# 601_USBHub-Grid-Part1.net
KiCad netlist of a schematic drawn in Altium Designer
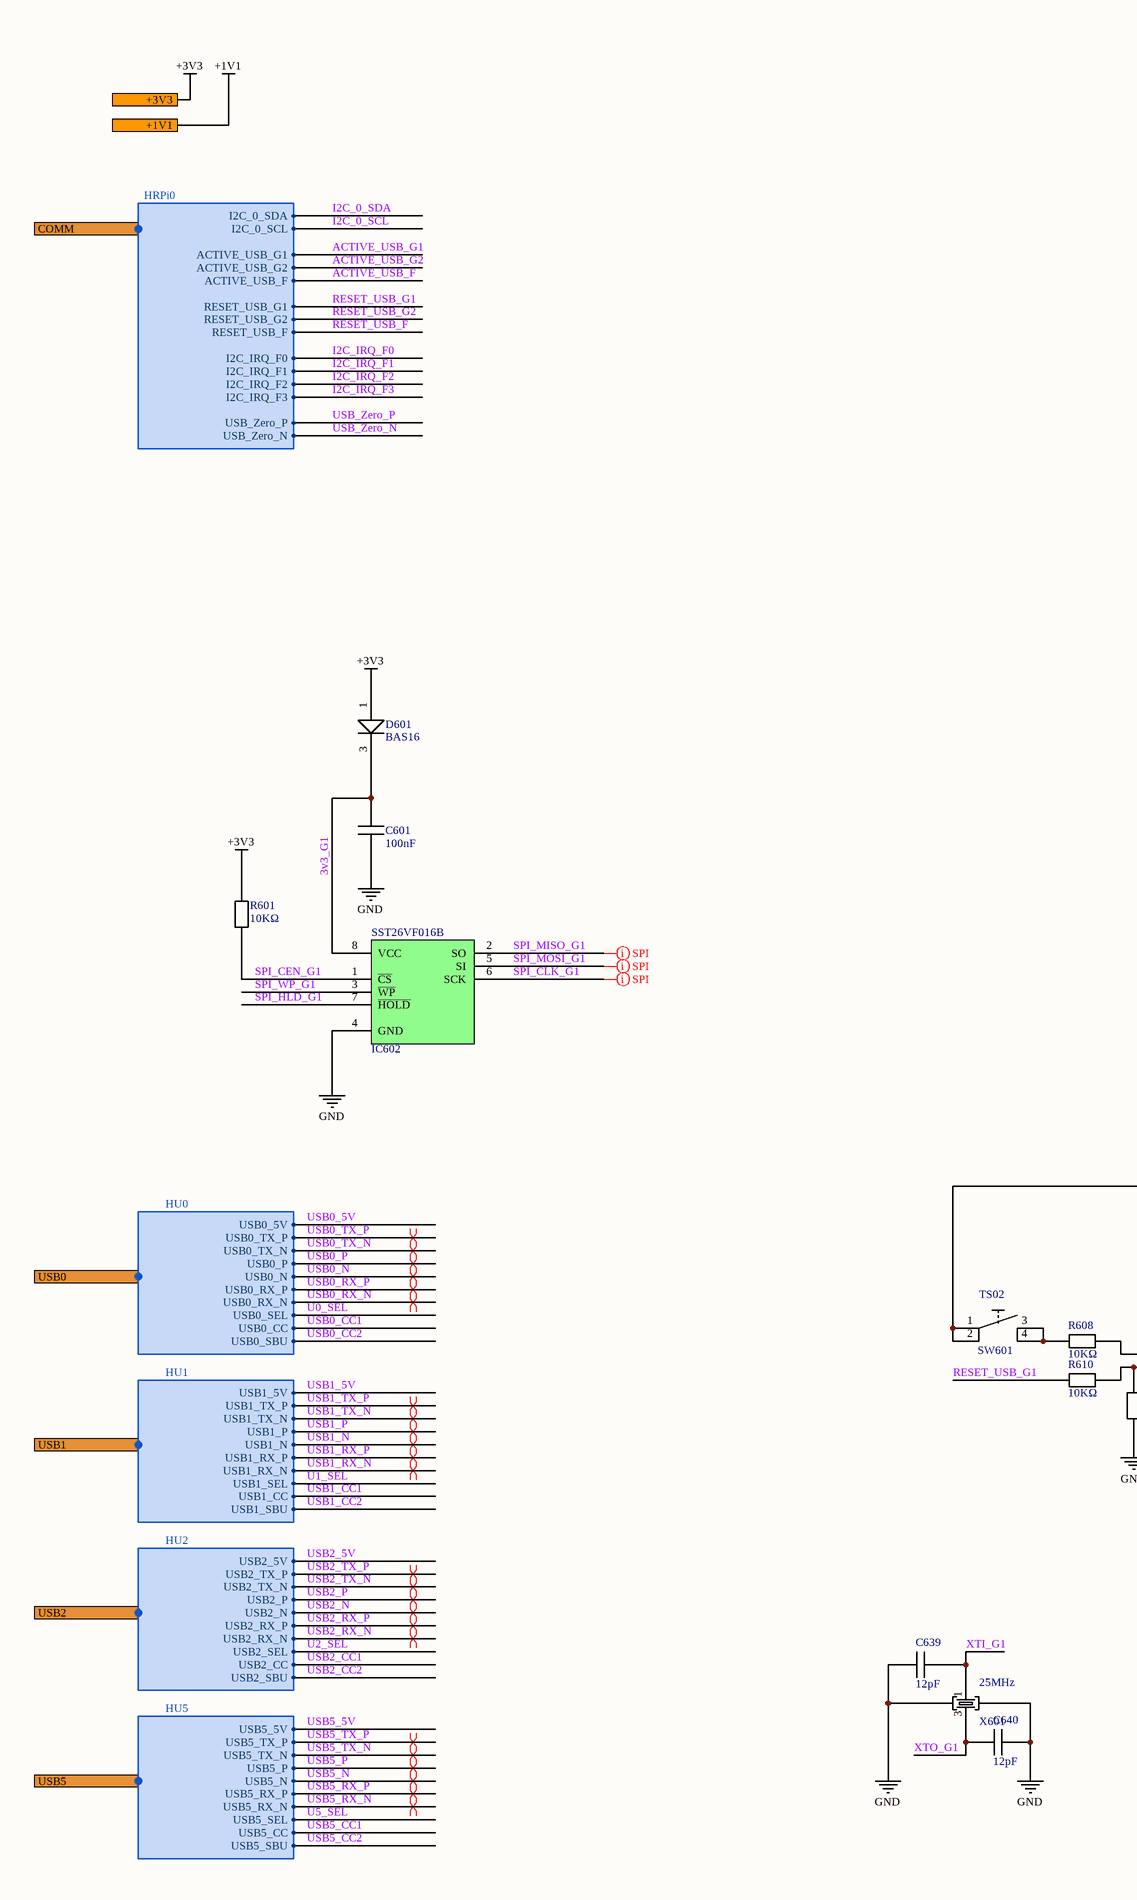
[diagram p0: 601_USBHub-Grid-Part1.SchDoc, left]
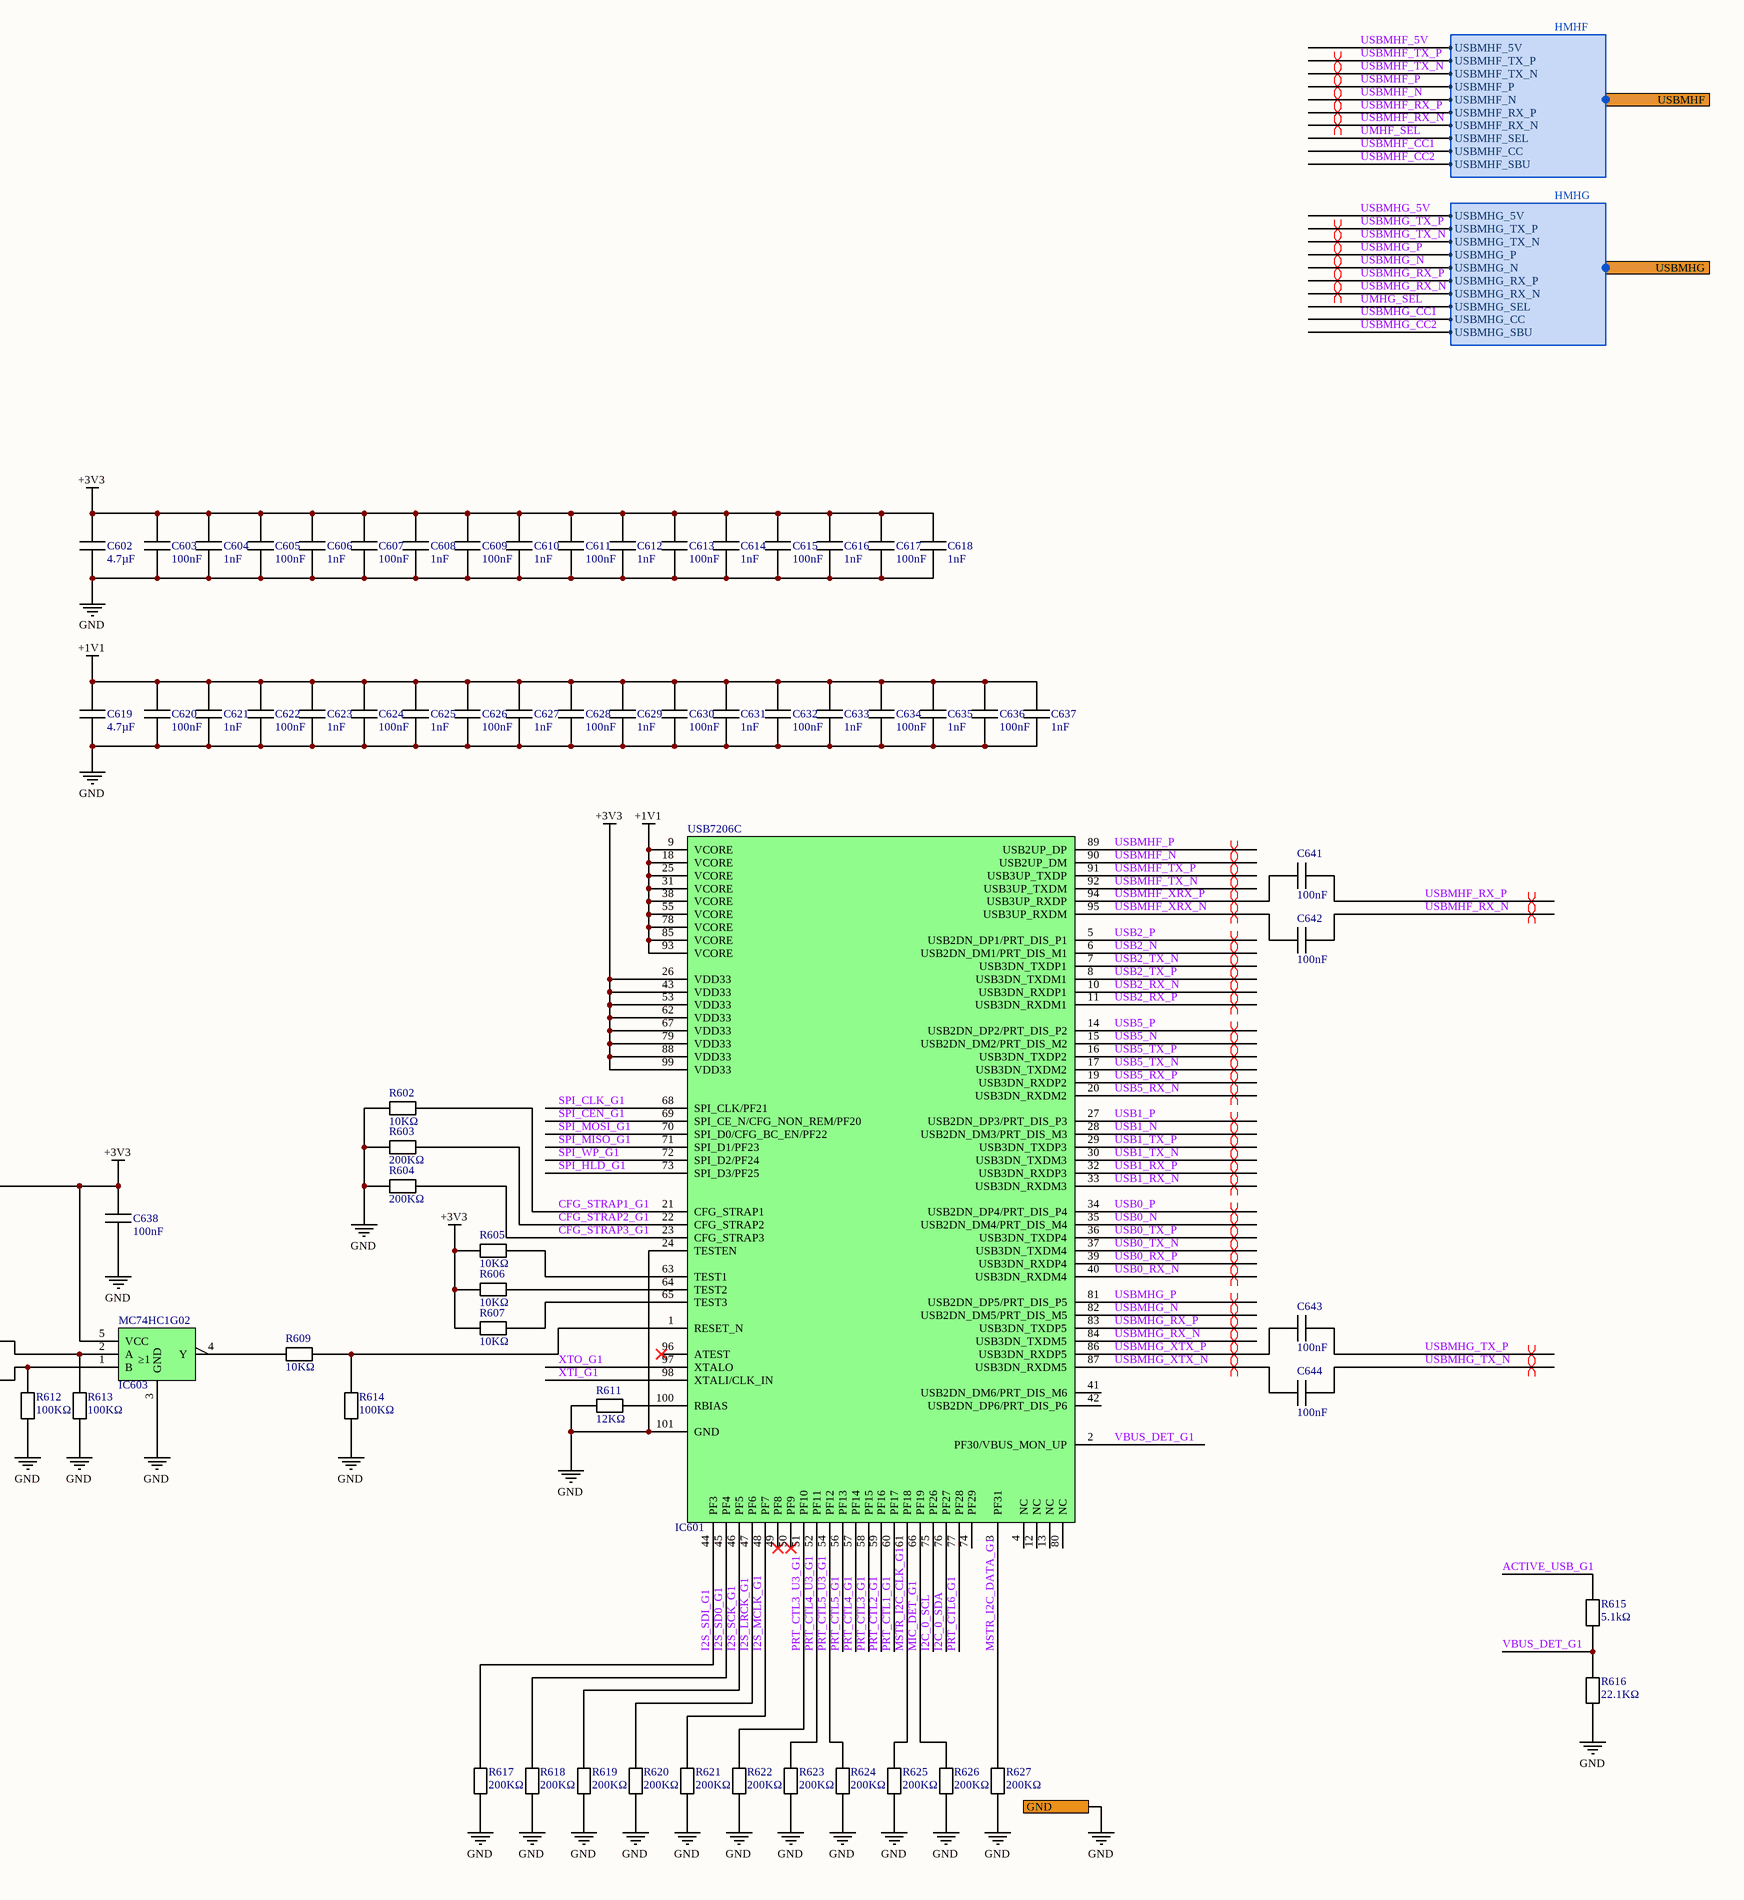
[diagram p1: 601_USBHub-Grid-Part1.SchDoc, right]

(export (version "E")
  (design (tool "Eeschema 10.0.6"))
  (components
    (comp (ref "C601")
      (value "100nF")
      (footprint "C0402")
      (description "100nF 16V 10% X7R")
      (fields
        (field (name "REFVAL") "100nF")
        (field (name "PART NUMBER") "CA0010")
        (field (name "MANFACTPART") "GCM155R71C104KA55D")
      )
      (libsource (lib "GTS_Database") (part "C"))
    )
    (comp (ref "C602")
      (value "4.7µF")
      (footprint "C0603")
      (description "4.7µF 16V 10% X5R")
      (fields
        (field (name "REFVAL") "4.7µF")
        (field (name "PART NUMBER") "CA0002")
        (field (name "MANFACTPART") "C1608X5R1C475K080AC")
      )
      (libsource (lib "GTS_Database") (part "C"))
    )
    (comp (ref "C603")
      (value "100nF")
      (footprint "C0402")
      (description "100nF 16V 10% X7R")
      (fields
        (field (name "REFVAL") "100nF")
        (field (name "PART NUMBER") "CA0010")
        (field (name "MANFACTPART") "GCM155R71C104KA55D")
      )
      (libsource (lib "GTS_Database") (part "C"))
    )
    (comp (ref "C604")
      (value "1nF")
      (footprint "C0402")
      (description "1nF 50V 1% C0G")
      (fields
        (field (name "REFVAL") "1nF")
        (field (name "PART NUMBER") "CA0031")
        (field (name "MANFACTPART") "GRT1555C1H102FA02D")
      )
      (libsource (lib "GTS_Database") (part "C"))
    )
    (comp (ref "C605")
      (value "100nF")
      (footprint "C0402")
      (description "100nF 16V 10% X7R")
      (fields
        (field (name "REFVAL") "100nF")
        (field (name "PART NUMBER") "CA0010")
        (field (name "MANFACTPART") "GCM155R71C104KA55D")
      )
      (libsource (lib "GTS_Database") (part "C"))
    )
    (comp (ref "C606")
      (value "1nF")
      (footprint "C0402")
      (description "1nF 50V 1% C0G")
      (fields
        (field (name "REFVAL") "1nF")
        (field (name "PART NUMBER") "CA0031")
        (field (name "MANFACTPART") "GRT1555C1H102FA02D")
      )
      (libsource (lib "GTS_Database") (part "C"))
    )
    (comp (ref "C607")
      (value "100nF")
      (footprint "C0402")
      (description "100nF 16V 10% X7R")
      (fields
        (field (name "REFVAL") "100nF")
        (field (name "PART NUMBER") "CA0010")
        (field (name "MANFACTPART") "GCM155R71C104KA55D")
      )
      (libsource (lib "GTS_Database") (part "C"))
    )
    (comp (ref "C608")
      (value "1nF")
      (footprint "C0402")
      (description "1nF 50V 1% C0G")
      (fields
        (field (name "REFVAL") "1nF")
        (field (name "PART NUMBER") "CA0031")
        (field (name "MANFACTPART") "GRT1555C1H102FA02D")
      )
      (libsource (lib "GTS_Database") (part "C"))
    )
    (comp (ref "C609")
      (value "100nF")
      (footprint "C0402")
      (description "100nF 16V 10% X7R")
      (fields
        (field (name "REFVAL") "100nF")
        (field (name "PART NUMBER") "CA0010")
        (field (name "MANFACTPART") "GCM155R71C104KA55D")
      )
      (libsource (lib "GTS_Database") (part "C"))
    )
    (comp (ref "C610")
      (value "1nF")
      (footprint "C0402")
      (description "1nF 50V 1% C0G")
      (fields
        (field (name "REFVAL") "1nF")
        (field (name "PART NUMBER") "CA0031")
        (field (name "MANFACTPART") "GRT1555C1H102FA02D")
      )
      (libsource (lib "GTS_Database") (part "C"))
    )
    (comp (ref "C611")
      (value "100nF")
      (footprint "C0402")
      (description "100nF 16V 10% X7R")
      (fields
        (field (name "REFVAL") "100nF")
        (field (name "PART NUMBER") "CA0010")
        (field (name "MANFACTPART") "GCM155R71C104KA55D")
      )
      (libsource (lib "GTS_Database") (part "C"))
    )
    (comp (ref "C612")
      (value "1nF")
      (footprint "C0402")
      (description "1nF 50V 1% C0G")
      (fields
        (field (name "REFVAL") "1nF")
        (field (name "PART NUMBER") "CA0031")
        (field (name "MANFACTPART") "GRT1555C1H102FA02D")
      )
      (libsource (lib "GTS_Database") (part "C"))
    )
    (comp (ref "C613")
      (value "100nF")
      (footprint "C0402")
      (description "100nF 16V 10% X7R")
      (fields
        (field (name "REFVAL") "100nF")
        (field (name "PART NUMBER") "CA0010")
        (field (name "MANFACTPART") "GCM155R71C104KA55D")
      )
      (libsource (lib "GTS_Database") (part "C"))
    )
    (comp (ref "C614")
      (value "1nF")
      (footprint "C0402")
      (description "1nF 50V 1% C0G")
      (fields
        (field (name "REFVAL") "1nF")
        (field (name "PART NUMBER") "CA0031")
        (field (name "MANFACTPART") "GRT1555C1H102FA02D")
      )
      (libsource (lib "GTS_Database") (part "C"))
    )
    (comp (ref "C615")
      (value "100nF")
      (footprint "C0402")
      (description "100nF 16V 10% X7R")
      (fields
        (field (name "REFVAL") "100nF")
        (field (name "PART NUMBER") "CA0010")
        (field (name "MANFACTPART") "GCM155R71C104KA55D")
      )
      (libsource (lib "GTS_Database") (part "C"))
    )
    (comp (ref "C616")
      (value "1nF")
      (footprint "C0402")
      (description "1nF 50V 1% C0G")
      (fields
        (field (name "REFVAL") "1nF")
        (field (name "PART NUMBER") "CA0031")
        (field (name "MANFACTPART") "GRT1555C1H102FA02D")
      )
      (libsource (lib "GTS_Database") (part "C"))
    )
    (comp (ref "C617")
      (value "100nF")
      (footprint "C0402")
      (description "100nF 16V 10% X7R")
      (fields
        (field (name "REFVAL") "100nF")
        (field (name "PART NUMBER") "CA0010")
        (field (name "MANFACTPART") "GCM155R71C104KA55D")
      )
      (libsource (lib "GTS_Database") (part "C"))
    )
    (comp (ref "C618")
      (value "1nF")
      (footprint "C0402")
      (description "1nF 50V 1% C0G")
      (fields
        (field (name "REFVAL") "1nF")
        (field (name "PART NUMBER") "CA0031")
        (field (name "MANFACTPART") "GRT1555C1H102FA02D")
      )
      (libsource (lib "GTS_Database") (part "C"))
    )
    (comp (ref "C619")
      (value "4.7µF")
      (footprint "C0603")
      (description "4.7µF 16V 10% X5R")
      (fields
        (field (name "REFVAL") "4.7µF")
        (field (name "PART NUMBER") "CA0002")
        (field (name "MANFACTPART") "C1608X5R1C475K080AC")
      )
      (libsource (lib "GTS_Database") (part "C"))
    )
    (comp (ref "C620")
      (value "100nF")
      (footprint "C0402")
      (description "100nF 16V 10% X7R")
      (fields
        (field (name "REFVAL") "100nF")
        (field (name "PART NUMBER") "CA0010")
        (field (name "MANFACTPART") "GCM155R71C104KA55D")
      )
      (libsource (lib "GTS_Database") (part "C"))
    )
    (comp (ref "C621")
      (value "1nF")
      (footprint "C0402")
      (description "1nF 50V 1% C0G")
      (fields
        (field (name "REFVAL") "1nF")
        (field (name "PART NUMBER") "CA0031")
        (field (name "MANFACTPART") "GRT1555C1H102FA02D")
      )
      (libsource (lib "GTS_Database") (part "C"))
    )
    (comp (ref "C622")
      (value "100nF")
      (footprint "C0402")
      (description "100nF 16V 10% X7R")
      (fields
        (field (name "REFVAL") "100nF")
        (field (name "PART NUMBER") "CA0010")
        (field (name "MANFACTPART") "GCM155R71C104KA55D")
      )
      (libsource (lib "GTS_Database") (part "C"))
    )
    (comp (ref "C623")
      (value "1nF")
      (footprint "C0402")
      (description "1nF 50V 1% C0G")
      (fields
        (field (name "REFVAL") "1nF")
        (field (name "PART NUMBER") "CA0031")
        (field (name "MANFACTPART") "GRT1555C1H102FA02D")
      )
      (libsource (lib "GTS_Database") (part "C"))
    )
    (comp (ref "C624")
      (value "100nF")
      (footprint "C0402")
      (description "100nF 16V 10% X7R")
      (fields
        (field (name "REFVAL") "100nF")
        (field (name "PART NUMBER") "CA0010")
        (field (name "MANFACTPART") "GCM155R71C104KA55D")
      )
      (libsource (lib "GTS_Database") (part "C"))
    )
    (comp (ref "C625")
      (value "1nF")
      (footprint "C0402")
      (description "1nF 50V 1% C0G")
      (fields
        (field (name "REFVAL") "1nF")
        (field (name "PART NUMBER") "CA0031")
        (field (name "MANFACTPART") "GRT1555C1H102FA02D")
      )
      (libsource (lib "GTS_Database") (part "C"))
    )
    (comp (ref "C626")
      (value "100nF")
      (footprint "C0402")
      (description "100nF 16V 10% X7R")
      (fields
        (field (name "REFVAL") "100nF")
        (field (name "PART NUMBER") "CA0010")
        (field (name "MANFACTPART") "GCM155R71C104KA55D")
      )
      (libsource (lib "GTS_Database") (part "C"))
    )
    (comp (ref "C627")
      (value "1nF")
      (footprint "C0402")
      (description "1nF 50V 1% C0G")
      (fields
        (field (name "REFVAL") "1nF")
        (field (name "PART NUMBER") "CA0031")
        (field (name "MANFACTPART") "GRT1555C1H102FA02D")
      )
      (libsource (lib "GTS_Database") (part "C"))
    )
    (comp (ref "C628")
      (value "100nF")
      (footprint "C0402")
      (description "100nF 16V 10% X7R")
      (fields
        (field (name "REFVAL") "100nF")
        (field (name "PART NUMBER") "CA0010")
        (field (name "MANFACTPART") "GCM155R71C104KA55D")
      )
      (libsource (lib "GTS_Database") (part "C"))
    )
    (comp (ref "C629")
      (value "1nF")
      (footprint "C0402")
      (description "1nF 50V 1% C0G")
      (fields
        (field (name "REFVAL") "1nF")
        (field (name "PART NUMBER") "CA0031")
        (field (name "MANFACTPART") "GRT1555C1H102FA02D")
      )
      (libsource (lib "GTS_Database") (part "C"))
    )
    (comp (ref "C630")
      (value "100nF")
      (footprint "C0402")
      (description "100nF 16V 10% X7R")
      (fields
        (field (name "REFVAL") "100nF")
        (field (name "PART NUMBER") "CA0010")
        (field (name "MANFACTPART") "GCM155R71C104KA55D")
      )
      (libsource (lib "GTS_Database") (part "C"))
    )
    (comp (ref "C631")
      (value "1nF")
      (footprint "C0402")
      (description "1nF 50V 1% C0G")
      (fields
        (field (name "REFVAL") "1nF")
        (field (name "PART NUMBER") "CA0031")
        (field (name "MANFACTPART") "GRT1555C1H102FA02D")
      )
      (libsource (lib "GTS_Database") (part "C"))
    )
    (comp (ref "C632")
      (value "100nF")
      (footprint "C0402")
      (description "100nF 16V 10% X7R")
      (fields
        (field (name "REFVAL") "100nF")
        (field (name "PART NUMBER") "CA0010")
        (field (name "MANFACTPART") "GCM155R71C104KA55D")
      )
      (libsource (lib "GTS_Database") (part "C"))
    )
    (comp (ref "C633")
      (value "1nF")
      (footprint "C0402")
      (description "1nF 50V 1% C0G")
      (fields
        (field (name "REFVAL") "1nF")
        (field (name "PART NUMBER") "CA0031")
        (field (name "MANFACTPART") "GRT1555C1H102FA02D")
      )
      (libsource (lib "GTS_Database") (part "C"))
    )
    (comp (ref "C634")
      (value "100nF")
      (footprint "C0402")
      (description "100nF 16V 10% X7R")
      (fields
        (field (name "REFVAL") "100nF")
        (field (name "PART NUMBER") "CA0010")
        (field (name "MANFACTPART") "GCM155R71C104KA55D")
      )
      (libsource (lib "GTS_Database") (part "C"))
    )
    (comp (ref "C635")
      (value "1nF")
      (footprint "C0402")
      (description "1nF 50V 1% C0G")
      (fields
        (field (name "REFVAL") "1nF")
        (field (name "PART NUMBER") "CA0031")
        (field (name "MANFACTPART") "GRT1555C1H102FA02D")
      )
      (libsource (lib "GTS_Database") (part "C"))
    )
    (comp (ref "C636")
      (value "100nF")
      (footprint "C0402")
      (description "100nF 16V 10% X7R")
      (fields
        (field (name "REFVAL") "100nF")
        (field (name "PART NUMBER") "CA0010")
        (field (name "MANFACTPART") "GCM155R71C104KA55D")
      )
      (libsource (lib "GTS_Database") (part "C"))
    )
    (comp (ref "C637")
      (value "1nF")
      (footprint "C0402")
      (description "1nF 50V 1% C0G")
      (fields
        (field (name "REFVAL") "1nF")
        (field (name "PART NUMBER") "CA0031")
        (field (name "MANFACTPART") "GRT1555C1H102FA02D")
      )
      (libsource (lib "GTS_Database") (part "C"))
    )
    (comp (ref "C638")
      (value "100nF")
      (footprint "C0402")
      (description "100nF 16V 10% X7R")
      (fields
        (field (name "REFVAL") "100nF")
        (field (name "PART NUMBER") "CA0010")
        (field (name "MANFACTPART") "GCM155R71C104KA55D")
      )
      (libsource (lib "GTS_Database") (part "C"))
    )
    (comp (ref "C639")
      (value "12pF")
      (footprint "C0402")
      (description "12pF 16V 1% C0G")
      (fields
        (field (name "REFVAL") "12pF")
        (field (name "PART NUMBER") "CA0059")
        (field (name "MANFACTPART") "VJ0402A120FXJCW1BC")
      )
      (libsource (lib "GTS_Database") (part "C"))
    )
    (comp (ref "C640")
      (value "12pF")
      (footprint "C0402")
      (description "12pF 16V 1% C0G")
      (fields
        (field (name "REFVAL") "12pF")
        (field (name "PART NUMBER") "CA0059")
        (field (name "MANFACTPART") "VJ0402A120FXJCW1BC")
      )
      (libsource (lib "GTS_Database") (part "C"))
    )
    (comp (ref "C641")
      (value "100nF")
      (footprint "C0402")
      (description "100nF 16V 10% X7R")
      (fields
        (field (name "REFVAL") "100nF")
        (field (name "PART NUMBER") "CA0010")
        (field (name "MANFACTPART") "GCM155R71C104KA55D")
      )
      (libsource (lib "GTS_Database") (part "C"))
    )
    (comp (ref "C642")
      (value "100nF")
      (footprint "C0402")
      (description "100nF 16V 10% X7R")
      (fields
        (field (name "REFVAL") "100nF")
        (field (name "PART NUMBER") "CA0010")
        (field (name "MANFACTPART") "GCM155R71C104KA55D")
      )
      (libsource (lib "GTS_Database") (part "C"))
    )
    (comp (ref "C643")
      (value "100nF")
      (footprint "C0402")
      (description "100nF 16V 10% X7R")
      (fields
        (field (name "REFVAL") "100nF")
        (field (name "PART NUMBER") "CA0010")
        (field (name "MANFACTPART") "GCM155R71C104KA55D")
      )
      (libsource (lib "GTS_Database") (part "C"))
    )
    (comp (ref "C644")
      (value "100nF")
      (footprint "C0402")
      (description "100nF 16V 10% X7R")
      (fields
        (field (name "REFVAL") "100nF")
        (field (name "PART NUMBER") "CA0010")
        (field (name "MANFACTPART") "GCM155R71C104KA55D")
      )
      (libsource (lib "GTS_Database") (part "C"))
    )
    (comp (ref "D601")
      (value "BAS16")
      (footprint "SOT-23")
      (description "Diodes - General Purpose, Power, Switching 100Vll Signal Switching Diodes 2A")
      (fields
        (field (name "REFVAL") "BAS16")
        (field (name "PART NUMBER") "DI0010")
        (field (name "MANFACTPART") "BAS16_R1_00001")
      )
      (libsource (lib "GTS_Database") (part "Ddefault_3P"))
    )
    (comp (ref "IC601")
      (value "USB7206C")
      (footprint "VQFN-100G_12X12")
      (description "6-Port USB 3.2 Gen 2 Controller Hub")
      (fields (field (name "REFVAL") "USB7206C") (field (name "PART NUMBER") "IC0065"))
      (libsource (lib "GTS_Database") (part "USB7206C"))
    )
    (comp (ref "IC602")
      (value "SST26VF016B")
      (footprint "SO-8")
      (description "16 Mbit Serial Quad I/O (SQI) Flash Memory")
      (fields
        (field (name "REFVAL") "SST26VF016B")
        (field (name "PART NUMBER") "IC0059")
        (field (name "MANFACTPART") "SST26VF016B-104I/SM")
      )
      (libsource (lib "GTS_Database") (part "SST26VF016B"))
    )
    (comp (ref "IC603")
      (value "MC74HC1G02")
      (footprint "TSOP-5")
      (description "Logic Gates 2-6V Single 2-Input NOR")
      (fields
        (field (name "REFVAL") "MC74HC1G02")
        (field (name "PART NUMBER") "IC0061")
        (field (name "MANFACTPART") "MC74HC1G02DTT1G")
      )
      (libsource (lib "GTS_Database") (part "MC74HC1G02"))
    )
    (comp (ref "R601")
      (value "10KΩ")
      (footprint "R0402")
      (description "10KΩ 1% 62.5mW")
      (fields
        (field (name "REFVAL") "10KΩ")
        (field (name "PART NUMBER") "RS0011")
        (field (name "MANFACTPART") "WR04X1002FTL")
      )
      (libsource (lib "GTS_Database") (part "R"))
    )
    (comp (ref "R602")
      (value "10KΩ")
      (footprint "R0402")
      (description "10KΩ 1% 62.5mW")
      (fields
        (field (name "REFVAL") "10KΩ")
        (field (name "PART NUMBER") "RS0011")
        (field (name "MANFACTPART") "WR04X1002FTL")
      )
      (libsource (lib "GTS_Database") (part "R"))
    )
    (comp (ref "R603")
      (value "200KΩ")
      (footprint "R0402")
      (description "200KΩ 1% 62.5mW 100PPM")
      (fields
        (field (name "REFVAL") "200KΩ")
        (field (name "PART NUMBER") "RS0045")
        (field (name "MANFACTPART") "CRG0402F200K")
      )
      (libsource (lib "GTS_Database") (part "R"))
    )
    (comp (ref "R604")
      (value "200KΩ")
      (footprint "R0402")
      (description "200KΩ 1% 62.5mW 100PPM")
      (fields
        (field (name "REFVAL") "200KΩ")
        (field (name "PART NUMBER") "RS0045")
        (field (name "MANFACTPART") "CRG0402F200K")
      )
      (libsource (lib "GTS_Database") (part "R"))
    )
    (comp (ref "R605")
      (value "10KΩ")
      (footprint "R0402")
      (description "10KΩ 1% 62.5mW")
      (fields
        (field (name "REFVAL") "10KΩ")
        (field (name "PART NUMBER") "RS0011")
        (field (name "MANFACTPART") "WR04X1002FTL")
      )
      (libsource (lib "GTS_Database") (part "R"))
    )
    (comp (ref "R606")
      (value "10KΩ")
      (footprint "R0402")
      (description "10KΩ 1% 62.5mW")
      (fields
        (field (name "REFVAL") "10KΩ")
        (field (name "PART NUMBER") "RS0011")
        (field (name "MANFACTPART") "WR04X1002FTL")
      )
      (libsource (lib "GTS_Database") (part "R"))
    )
    (comp (ref "R607")
      (value "10KΩ")
      (footprint "R0402")
      (description "10KΩ 1% 62.5mW")
      (fields
        (field (name "REFVAL") "10KΩ")
        (field (name "PART NUMBER") "RS0011")
        (field (name "MANFACTPART") "WR04X1002FTL")
      )
      (libsource (lib "GTS_Database") (part "R"))
    )
    (comp (ref "R608")
      (value "10KΩ")
      (footprint "R0402")
      (description "10KΩ 1% 62.5mW")
      (fields
        (field (name "REFVAL") "10KΩ")
        (field (name "PART NUMBER") "RS0011")
        (field (name "MANFACTPART") "WR04X1002FTL")
      )
      (libsource (lib "GTS_Database") (part "R"))
    )
    (comp (ref "R609")
      (value "10KΩ")
      (footprint "R0402")
      (description "10KΩ 1% 62.5mW")
      (fields
        (field (name "REFVAL") "10KΩ")
        (field (name "PART NUMBER") "RS0011")
        (field (name "MANFACTPART") "WR04X1002FTL")
      )
      (libsource (lib "GTS_Database") (part "R"))
    )
    (comp (ref "R610")
      (value "10KΩ")
      (footprint "R0402")
      (description "10KΩ 1% 62.5mW")
      (fields
        (field (name "REFVAL") "10KΩ")
        (field (name "PART NUMBER") "RS0011")
        (field (name "MANFACTPART") "WR04X1002FTL")
      )
      (libsource (lib "GTS_Database") (part "R"))
    )
    (comp (ref "R611")
      (value "12KΩ")
      (footprint "R0402")
      (description "12KΩ 1% 62.5mW")
      (fields
        (field (name "REFVAL") "12KΩ")
        (field (name "PART NUMBER") "RS0015")
        (field (name "MANFACTPART") "RC0402FR-1312KL")
      )
      (libsource (lib "GTS_Database") (part "R"))
    )
    (comp (ref "R612")
      (value "100KΩ")
      (footprint "R0402")
      (description "100KΩ 1% 62.5mW 100PPM")
      (fields
        (field (name "REFVAL") "100KΩ")
        (field (name "PART NUMBER") "RS0036")
        (field (name "MANFACTPART") "AC0402FR-13100KL")
      )
      (libsource (lib "GTS_Database") (part "R"))
    )
    (comp (ref "R613")
      (value "100KΩ")
      (footprint "R0402")
      (description "100KΩ 1% 62.5mW 100PPM")
      (fields
        (field (name "REFVAL") "100KΩ")
        (field (name "PART NUMBER") "RS0036")
        (field (name "MANFACTPART") "AC0402FR-13100KL")
      )
      (libsource (lib "GTS_Database") (part "R"))
    )
    (comp (ref "R614")
      (value "100KΩ")
      (footprint "R0402")
      (description "100KΩ 1% 62.5mW 100PPM")
      (fields
        (field (name "REFVAL") "100KΩ")
        (field (name "PART NUMBER") "RS0036")
        (field (name "MANFACTPART") "AC0402FR-13100KL")
      )
      (libsource (lib "GTS_Database") (part "R"))
    )
    (comp (ref "R615")
      (value "5.1kΩ")
      (footprint "R0402")
      (description "5.1KΩ 1% 62.5mW 100PPM")
      (fields
        (field (name "REFVAL") "5.1kΩ")
        (field (name "PART NUMBER") "RS0038")
        (field (name "MANFACTPART") "CRCW04025K10FKEDC")
      )
      (libsource (lib "GTS_Database") (part "R"))
    )
    (comp (ref "R616")
      (value "22.1KΩ")
      (footprint "R0603")
      (description "22.1KΩ 1% 100mW 100PPM")
      (fields
        (field (name "REFVAL") "22.1KΩ")
        (field (name "PART NUMBER") "RS0040")
        (field (name "MANFACTPART") "RC0603FR-0722K1L")
      )
      (libsource (lib "GTS_Database") (part "R"))
    )
    (comp (ref "R617")
      (value "200KΩ")
      (footprint "R0402")
      (description "200KΩ 1% 62.5mW 100PPM")
      (fields
        (field (name "REFVAL") "200KΩ")
        (field (name "PART NUMBER") "RS0045")
        (field (name "MANFACTPART") "CRG0402F200K")
      )
      (libsource (lib "GTS_Database") (part "R"))
    )
    (comp (ref "R618")
      (value "200KΩ")
      (footprint "R0402")
      (description "200KΩ 1% 62.5mW 100PPM")
      (fields
        (field (name "REFVAL") "200KΩ")
        (field (name "PART NUMBER") "RS0045")
        (field (name "MANFACTPART") "CRG0402F200K")
      )
      (libsource (lib "GTS_Database") (part "R"))
    )
    (comp (ref "R619")
      (value "200KΩ")
      (footprint "R0402")
      (description "200KΩ 1% 62.5mW 100PPM")
      (fields
        (field (name "REFVAL") "200KΩ")
        (field (name "PART NUMBER") "RS0045")
        (field (name "MANFACTPART") "CRG0402F200K")
      )
      (libsource (lib "GTS_Database") (part "R"))
    )
    (comp (ref "R620")
      (value "200KΩ")
      (footprint "R0402")
      (description "200KΩ 1% 62.5mW 100PPM")
      (fields
        (field (name "REFVAL") "200KΩ")
        (field (name "PART NUMBER") "RS0045")
        (field (name "MANFACTPART") "CRG0402F200K")
      )
      (libsource (lib "GTS_Database") (part "R"))
    )
    (comp (ref "R621")
      (value "200KΩ")
      (footprint "R0402")
      (description "200KΩ 1% 62.5mW 100PPM")
      (fields
        (field (name "REFVAL") "200KΩ")
        (field (name "PART NUMBER") "RS0045")
        (field (name "MANFACTPART") "CRG0402F200K")
      )
      (libsource (lib "GTS_Database") (part "R"))
    )
    (comp (ref "R622")
      (value "200KΩ")
      (footprint "R0402")
      (description "200KΩ 1% 62.5mW 100PPM")
      (fields
        (field (name "REFVAL") "200KΩ")
        (field (name "PART NUMBER") "RS0045")
        (field (name "MANFACTPART") "CRG0402F200K")
      )
      (libsource (lib "GTS_Database") (part "R"))
    )
    (comp (ref "R623")
      (value "200KΩ")
      (footprint "R0402")
      (description "200KΩ 1% 62.5mW 100PPM")
      (fields
        (field (name "REFVAL") "200KΩ")
        (field (name "PART NUMBER") "RS0045")
        (field (name "MANFACTPART") "CRG0402F200K")
      )
      (libsource (lib "GTS_Database") (part "R"))
    )
    (comp (ref "R624")
      (value "200KΩ")
      (footprint "R0402")
      (description "200KΩ 1% 62.5mW 100PPM")
      (fields
        (field (name "REFVAL") "200KΩ")
        (field (name "PART NUMBER") "RS0045")
        (field (name "MANFACTPART") "CRG0402F200K")
      )
      (libsource (lib "GTS_Database") (part "R"))
    )
    (comp (ref "R625")
      (value "200KΩ")
      (footprint "R0402")
      (description "200KΩ 1% 62.5mW 100PPM")
      (fields
        (field (name "REFVAL") "200KΩ")
        (field (name "PART NUMBER") "RS0045")
        (field (name "MANFACTPART") "CRG0402F200K")
      )
      (libsource (lib "GTS_Database") (part "R"))
    )
    (comp (ref "R626")
      (value "200KΩ")
      (footprint "R0402")
      (description "200KΩ 1% 62.5mW 100PPM")
      (fields
        (field (name "REFVAL") "200KΩ")
        (field (name "PART NUMBER") "RS0045")
        (field (name "MANFACTPART") "CRG0402F200K")
      )
      (libsource (lib "GTS_Database") (part "R"))
    )
    (comp (ref "R627")
      (value "200KΩ")
      (footprint "R0402")
      (description "200KΩ 1% 62.5mW 100PPM")
      (fields
        (field (name "REFVAL") "200KΩ")
        (field (name "PART NUMBER") "RS0045")
        (field (name "MANFACTPART") "CRG0402F200K")
      )
      (libsource (lib "GTS_Database") (part "R"))
    )
    (comp (ref "SW601")
      (value "TS02")
      (footprint "TS02")
      (description "TACTILE SWITCH SPST")
      (fields
        (field (name "REFVAL") "TS02")
        (field (name "PART NUMBER") "SW0005")
        (field (name "MANFACTPART") "TS02-66-50-BK-160-SCR-D")
      )
      (libsource (lib "GTS_Database") (part "SPST-2-4"))
    )
    (comp (ref "X601")
      (value "25MHz")
      (footprint "403W")
      (description "25MHz 8pF 20PPM")
      (fields
        (field (name "REFVAL") "25MHz")
        (field (name "PART NUMBER") "CR0003")
        (field (name "MANFACTPART") "403WF25012IK")
      )
      (libsource (lib "GTS_Database") (part "Crystal_1_3"))
    )
  )
  (nets
    (net (code "8") (name "+1V1") (class "Default")
      (node (ref "C619") (pin "1") (pinfunction "1_1") (pintype "passive"))
      (node (ref "C620") (pin "1") (pinfunction "1_1") (pintype "passive"))
      (node (ref "C621") (pin "1") (pinfunction "1_1") (pintype "passive"))
      (node (ref "C622") (pin "1") (pinfunction "1_1") (pintype "passive"))
      (node (ref "C623") (pin "1") (pinfunction "1_1") (pintype "passive"))
      (node (ref "C624") (pin "1") (pinfunction "1_1") (pintype "passive"))
      (node (ref "C625") (pin "1") (pinfunction "1_1") (pintype "passive"))
      (node (ref "C626") (pin "1") (pinfunction "1_1") (pintype "passive"))
      (node (ref "C627") (pin "1") (pinfunction "1_1") (pintype "passive"))
      (node (ref "C628") (pin "1") (pinfunction "1_1") (pintype "passive"))
      (node (ref "C629") (pin "1") (pinfunction "1_1") (pintype "passive"))
      (node (ref "C630") (pin "1") (pinfunction "1_1") (pintype "passive"))
      (node (ref "C631") (pin "1") (pinfunction "1_1") (pintype "passive"))
      (node (ref "C632") (pin "1") (pinfunction "1_1") (pintype "passive"))
      (node (ref "C633") (pin "1") (pinfunction "1_1") (pintype "passive"))
      (node (ref "C634") (pin "1") (pinfunction "1_1") (pintype "passive"))
      (node (ref "C635") (pin "1") (pinfunction "1_1") (pintype "passive"))
      (node (ref "C636") (pin "1") (pinfunction "1_1") (pintype "passive"))
      (node (ref "C637") (pin "1") (pinfunction "1_1") (pintype "passive"))
      (node (ref "IC601") (pin "18") (pinfunction "VCORE_18") (pintype "passive"))
      (node (ref "IC601") (pin "25") (pinfunction "VCORE_25") (pintype "passive"))
      (node (ref "IC601") (pin "31") (pinfunction "VCORE_31") (pintype "passive"))
      (node (ref "IC601") (pin "38") (pinfunction "VCORE_38") (pintype "passive"))
      (node (ref "IC601") (pin "55") (pinfunction "VCORE_55") (pintype "passive"))
      (node (ref "IC601") (pin "78") (pinfunction "VCORE_78") (pintype "passive"))
      (node (ref "IC601") (pin "85") (pinfunction "VCORE_85") (pintype "passive"))
      (node (ref "IC601") (pin "9") (pinfunction "VCORE_9") (pintype "passive"))
      (node (ref "IC601") (pin "93") (pinfunction "VCORE_93") (pintype "passive"))
    )
    (net (code "9") (name "+3V3") (class "Default")
      (node (ref "C602") (pin "1") (pinfunction "1_1") (pintype "passive"))
      (node (ref "C603") (pin "1") (pinfunction "1_1") (pintype "passive"))
      (node (ref "C604") (pin "1") (pinfunction "1_1") (pintype "passive"))
      (node (ref "C605") (pin "1") (pinfunction "1_1") (pintype "passive"))
      (node (ref "C606") (pin "1") (pinfunction "1_1") (pintype "passive"))
      (node (ref "C607") (pin "1") (pinfunction "1_1") (pintype "passive"))
      (node (ref "C608") (pin "1") (pinfunction "1_1") (pintype "passive"))
      (node (ref "C609") (pin "1") (pinfunction "1_1") (pintype "passive"))
      (node (ref "C610") (pin "1") (pinfunction "1_1") (pintype "passive"))
      (node (ref "C611") (pin "1") (pinfunction "1_1") (pintype "passive"))
      (node (ref "C612") (pin "1") (pinfunction "1_1") (pintype "passive"))
      (node (ref "C613") (pin "1") (pinfunction "1_1") (pintype "passive"))
      (node (ref "C614") (pin "1") (pinfunction "1_1") (pintype "passive"))
      (node (ref "C615") (pin "1") (pinfunction "1_1") (pintype "passive"))
      (node (ref "C616") (pin "1") (pinfunction "1_1") (pintype "passive"))
      (node (ref "C617") (pin "1") (pinfunction "1_1") (pintype "passive"))
      (node (ref "C618") (pin "1") (pinfunction "1_1") (pintype "passive"))
      (node (ref "C638") (pin "1") (pinfunction "1_1") (pintype "passive"))
      (node (ref "D601") (pin "1") (pinfunction "A_1") (pintype "passive"))
      (node (ref "IC601") (pin "26") (pinfunction "VDD33_26") (pintype "passive"))
      (node (ref "IC601") (pin "43") (pinfunction "VDD33_43") (pintype "passive"))
      (node (ref "IC601") (pin "53") (pinfunction "VDD33_53") (pintype "passive"))
      (node (ref "IC601") (pin "62") (pinfunction "VDD33_62") (pintype "passive"))
      (node (ref "IC601") (pin "67") (pinfunction "VDD33_67") (pintype "passive"))
      (node (ref "IC601") (pin "79") (pinfunction "VDD33_79") (pintype "passive"))
      (node (ref "IC601") (pin "88") (pinfunction "VDD33_88") (pintype "passive"))
      (node (ref "IC601") (pin "99") (pinfunction "VDD33_99") (pintype "passive"))
      (node (ref "IC603") (pin "5") (pinfunction "VCC_5") (pintype "passive"))
      (node (ref "R601") (pin "2") (pinfunction "2_2") (pintype "passive"))
      (node (ref "R605") (pin "1") (pinfunction "1_1") (pintype "passive"))
      (node (ref "R606") (pin "1") (pinfunction "1_1") (pintype "passive"))
      (node (ref "R607") (pin "1") (pinfunction "1_1") (pintype "passive"))
      (node (ref "SW601") (pin "1") (pinfunction "1_1") (pintype "passive"))
      (node (ref "SW601") (pin "2") (pinfunction "2_2") (pintype "passive"))
    )
    (net (code "10") (name "/3v3_G1") (class "Default")
      (node (ref "C601") (pin "1") (pinfunction "1_1") (pintype "passive"))
      (node (ref "D601") (pin "3") (pinfunction "K_3") (pintype "passive"))
      (node (ref "IC602") (pin "8") (pinfunction "VCC_8") (pintype "passive"))
    )
    (net (code "12") (name "/ACTIVE_USB_G1") (class "Default")
      (node (ref "R615") (pin "2") (pinfunction "2_2") (pintype "passive"))
    )
    (net (code "14") (name "/CFG_STRAP1_G1") (class "Default")
      (node (ref "IC601") (pin "21") (pinfunction "CFG_STRAP1_21") (pintype "passive"))
      (node (ref "R602") (pin "1") (pinfunction "1_1") (pintype "passive"))
    )
    (net (code "15") (name "/CFG_STRAP2_G1") (class "Default")
      (node (ref "IC601") (pin "22") (pinfunction "CFG_STRAP2_22") (pintype "passive"))
      (node (ref "R603") (pin "2") (pinfunction "2_2") (pintype "passive"))
    )
    (net (code "16") (name "/CFG_STRAP3_G1") (class "Default")
      (node (ref "IC601") (pin "23") (pinfunction "CFG_STRAP3_23") (pintype "passive"))
      (node (ref "R604") (pin "2") (pinfunction "2_2") (pintype "passive"))
    )
    (net (code "17") (name "/I2C_0_SCL") (class "Default")
      (node (ref "IC601") (pin "75") (pinfunction "PF26_75") (pintype "passive"))
    )
    (net (code "18") (name "/I2C_0_SDA") (class "Default")
      (node (ref "IC601") (pin "76") (pinfunction "PF27_76") (pintype "passive"))
    )
    (net (code "23") (name "/I2S_LRCK_G1") (class "Default")
      (node (ref "IC601") (pin "47") (pinfunction "PF6_47") (pintype "passive"))
      (node (ref "R620") (pin "2") (pinfunction "2_2") (pintype "passive"))
    )
    (net (code "24") (name "/I2S_MCLK_G1") (class "Default")
      (node (ref "IC601") (pin "48") (pinfunction "PF7_48") (pintype "passive"))
      (node (ref "R621") (pin "2") (pinfunction "2_2") (pintype "passive"))
    )
    (net (code "25") (name "/I2S_SCK_G1") (class "Default")
      (node (ref "IC601") (pin "46") (pinfunction "PF5_46") (pintype "passive"))
      (node (ref "R619") (pin "2") (pinfunction "2_2") (pintype "passive"))
    )
    (net (code "26") (name "/I2S_SD0_G1") (class "Default")
      (node (ref "IC601") (pin "45") (pinfunction "PF4_45") (pintype "passive"))
      (node (ref "R618") (pin "2") (pinfunction "2_2") (pintype "passive"))
    )
    (net (code "27") (name "/I2S_SDI_G1") (class "Default")
      (node (ref "IC601") (pin "44") (pinfunction "PF3_44") (pintype "passive"))
      (node (ref "R617") (pin "2") (pinfunction "2_2") (pintype "passive"))
    )
    (net (code "28") (name "/MIC_DET_G1") (class "Default")
      (node (ref "IC601") (pin "66") (pinfunction "PF19_66") (pintype "passive"))
      (node (ref "R626") (pin "2") (pinfunction "2_2") (pintype "passive"))
    )
    (net (code "29") (name "/MSTR_I2C_CLK_G1") (class "Default")
      (node (ref "IC601") (pin "61") (pinfunction "PF18_61") (pintype "passive"))
      (node (ref "R625") (pin "2") (pinfunction "2_2") (pintype "passive"))
    )
    (net (code "30") (name "/MSTR_I2C_DATA_G1") (class "Default")
      (node (ref "IC601") (pin "3") (pinfunction "PF31_3") (pintype "passive"))
      (node (ref "R627") (pin "2") (pinfunction "2_2") (pintype "passive"))
    )
    (net (code "31") (name "/PRT_CTL1_G1") (class "Default")
      (node (ref "IC601") (pin "60") (pinfunction "PF17_60") (pintype "passive"))
    )
    (net (code "32") (name "/PRT_CTL2_G1") (class "Default")
      (node (ref "IC601") (pin "59") (pinfunction "PF16_59") (pintype "passive"))
    )
    (net (code "33") (name "/PRT_CTL3_G1") (class "Default")
      (node (ref "IC601") (pin "58") (pinfunction "PF15_58") (pintype "passive"))
    )
    (net (code "34") (name "/PRT_CTL3_U3_G1") (class "Default")
      (node (ref "IC601") (pin "51") (pinfunction "PF10_51") (pintype "passive"))
      (node (ref "R622") (pin "2") (pinfunction "2_2") (pintype "passive"))
    )
    (net (code "35") (name "/PRT_CTL4_G1") (class "Default")
      (node (ref "IC601") (pin "57") (pinfunction "PF14_57") (pintype "passive"))
    )
    (net (code "36") (name "/PRT_CTL4_U3_G1") (class "Default")
      (node (ref "IC601") (pin "52") (pinfunction "PF11_52") (pintype "passive"))
      (node (ref "R623") (pin "2") (pinfunction "2_2") (pintype "passive"))
    )
    (net (code "37") (name "/PRT_CTL5_G1") (class "Default")
      (node (ref "IC601") (pin "56") (pinfunction "PF13_56") (pintype "passive"))
    )
    (net (code "38") (name "/PRT_CTL5_U3_G1") (class "Default")
      (node (ref "IC601") (pin "54") (pinfunction "PF12_54") (pintype "passive"))
      (node (ref "R624") (pin "2") (pinfunction "2_2") (pintype "passive"))
    )
    (net (code "39") (name "/PRT_CTL6_G1") (class "Default")
      (node (ref "IC601") (pin "77") (pinfunction "PF28_77") (pintype "passive"))
    )
    (net (code "41") (name "/RESET_USB_G1") (class "Default")
      (node (ref "R610") (pin "2") (pinfunction "2_2") (pintype "passive"))
    )
    (net (code "43") (name "/SPI_CEN_G1") (class "Default")
      (node (ref "IC601") (pin "69") (pinfunction "SPI_CE_N/CFG_NON_REM/PF20_69") (pintype "passive"))
      (node (ref "IC602") (pin "1") (pinfunction "CS_1") (pintype "passive"))
      (node (ref "R601") (pin "1") (pinfunction "1_1") (pintype "passive"))
    )
    (net (code "44") (name "/SPI_CLK_G1") (class "Default")
      (node (ref "IC601") (pin "68") (pinfunction "SPI_CLK/PF21_68") (pintype "passive"))
      (node (ref "IC602") (pin "6") (pinfunction "SCK_6") (pintype "passive"))
    )
    (net (code "45") (name "/SPI_HLD_G1") (class "Default")
      (node (ref "IC601") (pin "73") (pinfunction "SPI_D3/PF25_73") (pintype "passive"))
      (node (ref "IC602") (pin "7") (pinfunction "HOLD_7") (pintype "passive"))
    )
    (net (code "46") (name "/SPI_MISO_G1") (class "Default")
      (node (ref "IC601") (pin "71") (pinfunction "SPI_D1/PF23_71") (pintype "passive"))
      (node (ref "IC602") (pin "2") (pinfunction "SO_2") (pintype "passive"))
    )
    (net (code "47") (name "/SPI_MOSI_G1") (class "Default")
      (node (ref "IC601") (pin "70") (pinfunction "SPI_D0/CFG_BC_EN/PF22_70") (pintype "passive"))
      (node (ref "IC602") (pin "5") (pinfunction "SI_5") (pintype "passive"))
    )
    (net (code "48") (name "/SPI_WP_G1") (class "Default")
      (node (ref "IC601") (pin "72") (pinfunction "SPI_D2/PF24_72") (pintype "passive"))
      (node (ref "IC602") (pin "3") (pinfunction "WP_3") (pintype "passive"))
    )
    (net (code "58") (name "/USB0_N") (class "Default")
      (node (ref "IC601") (pin "35") (pinfunction "USB2DN_DM4/PRT_DIS_M4_35") (pintype "passive"))
    )
    (net (code "59") (name "/USB0_P") (class "Default")
      (node (ref "IC601") (pin "34") (pinfunction "USB2DN_DP4/PRT_DIS_P4_34") (pintype "passive"))
    )
    (net (code "60") (name "/USB0_RX_N") (class "Default")
      (node (ref "IC601") (pin "40") (pinfunction "USB3DN_RXDM4_40") (pintype "passive"))
    )
    (net (code "61") (name "/USB0_RX_P") (class "Default")
      (node (ref "IC601") (pin "39") (pinfunction "USB3DN_RXDP4_39") (pintype "passive"))
    )
    (net (code "62") (name "/USB0_TX_N") (class "Default")
      (node (ref "IC601") (pin "37") (pinfunction "USB3DN_TXDM4_37") (pintype "passive"))
    )
    (net (code "63") (name "/USB0_TX_P") (class "Default")
      (node (ref "IC601") (pin "36") (pinfunction "USB3DN_TXDP4_36") (pintype "passive"))
    )
    (net (code "67") (name "/USB1_N") (class "Default")
      (node (ref "IC601") (pin "28") (pinfunction "USB2DN_DM3/PRT_DIS_M3_28") (pintype "passive"))
    )
    (net (code "68") (name "/USB1_P") (class "Default")
      (node (ref "IC601") (pin "27") (pinfunction "USB2DN_DP3/PRT_DIS_P3_27") (pintype "passive"))
    )
    (net (code "69") (name "/USB1_RX_N") (class "Default")
      (node (ref "IC601") (pin "33") (pinfunction "USB3DN_RXDM3_33") (pintype "passive"))
    )
    (net (code "70") (name "/USB1_RX_P") (class "Default")
      (node (ref "IC601") (pin "32") (pinfunction "USB3DN_RXDP3_32") (pintype "passive"))
    )
    (net (code "71") (name "/USB1_TX_N") (class "Default")
      (node (ref "IC601") (pin "30") (pinfunction "USB3DN_TXDM3_30") (pintype "passive"))
    )
    (net (code "72") (name "/USB1_TX_P") (class "Default")
      (node (ref "IC601") (pin "29") (pinfunction "USB3DN_TXDP3_29") (pintype "passive"))
    )
    (net (code "76") (name "/USB2_N") (class "Default")
      (node (ref "IC601") (pin "6") (pinfunction "USB2DN_DM1/PRT_DIS_M1_6") (pintype "passive"))
    )
    (net (code "77") (name "/USB2_P") (class "Default")
      (node (ref "IC601") (pin "5") (pinfunction "USB2DN_DP1/PRT_DIS_P1_5") (pintype "passive"))
    )
    (net (code "78") (name "/USB2_RX_N") (class "Default")
      (node (ref "IC601") (pin "10") (pinfunction "USB3DN_RXDP1_10") (pintype "passive"))
    )
    (net (code "79") (name "/USB2_RX_P") (class "Default")
      (node (ref "IC601") (pin "11") (pinfunction "USB3DN_RXDM1_11") (pintype "passive"))
    )
    (net (code "80") (name "/USB2_TX_N") (class "Default")
      (node (ref "IC601") (pin "7") (pinfunction "USB3DN_TXDP1_7") (pintype "passive"))
    )
    (net (code "81") (name "/USB2_TX_P") (class "Default")
      (node (ref "IC601") (pin "8") (pinfunction "USB3DN_TXDM1_8") (pintype "passive"))
    )
    (net (code "85") (name "/USB5_N") (class "Default")
      (node (ref "IC601") (pin "15") (pinfunction "USB2DN_DM2/PRT_DIS_M2_15") (pintype "passive"))
    )
    (net (code "86") (name "/USB5_P") (class "Default")
      (node (ref "IC601") (pin "14") (pinfunction "USB2DN_DP2/PRT_DIS_P2_14") (pintype "passive"))
    )
    (net (code "87") (name "/USB5_RX_N") (class "Default")
      (node (ref "IC601") (pin "20") (pinfunction "USB3DN_RXDM2_20") (pintype "passive"))
    )
    (net (code "88") (name "/USB5_RX_P") (class "Default")
      (node (ref "IC601") (pin "19") (pinfunction "USB3DN_RXDP2_19") (pintype "passive"))
    )
    (net (code "89") (name "/USB5_TX_N") (class "Default")
      (node (ref "IC601") (pin "17") (pinfunction "USB3DN_TXDM2_17") (pintype "passive"))
    )
    (net (code "90") (name "/USB5_TX_P") (class "Default")
      (node (ref "IC601") (pin "16") (pinfunction "USB3DN_TXDP2_16") (pintype "passive"))
    )
    (net (code "94") (name "/USBMHF_N") (class "Default")
      (node (ref "IC601") (pin "90") (pinfunction "USB2UP_DM_90") (pintype "passive"))
    )
    (net (code "95") (name "/USBMHF_P") (class "Default")
      (node (ref "IC601") (pin "89") (pinfunction "USB2UP_DP_89") (pintype "passive"))
    )
    (net (code "96") (name "/USBMHF_RX_N") (class "Default")
      (node (ref "C642") (pin "2") (pinfunction "2_2") (pintype "passive"))
    )
    (net (code "97") (name "/USBMHF_RX_P") (class "Default")
      (node (ref "C641") (pin "2") (pinfunction "2_2") (pintype "passive"))
    )
    (net (code "98") (name "/USBMHF_TX_N") (class "Default")
      (node (ref "IC601") (pin "92") (pinfunction "USB3UP_TXDM_92") (pintype "passive"))
    )
    (net (code "99") (name "/USBMHF_TX_P") (class "Default")
      (node (ref "IC601") (pin "91") (pinfunction "USB3UP_TXDP_91") (pintype "passive"))
    )
    (net (code "100") (name "/USBMHF_XRX_N") (class "Default")
      (node (ref "C642") (pin "1") (pinfunction "1_1") (pintype "passive"))
      (node (ref "IC601") (pin "95") (pinfunction "USB3UP_RXDM_95") (pintype "passive"))
    )
    (net (code "101") (name "/USBMHF_XRX_P") (class "Default")
      (node (ref "C641") (pin "1") (pinfunction "1_1") (pintype "passive"))
      (node (ref "IC601") (pin "94") (pinfunction "USB3UP_RXDP_94") (pintype "passive"))
    )
    (net (code "105") (name "/USBMHG_N") (class "Default")
      (node (ref "IC601") (pin "82") (pinfunction "USB2DN_DM5/PRT_DIS_M5_82") (pintype "passive"))
    )
    (net (code "106") (name "/USBMHG_P") (class "Default")
      (node (ref "IC601") (pin "81") (pinfunction "USB2DN_DP5/PRT_DIS_P5_81") (pintype "passive"))
    )
    (net (code "107") (name "/USBMHG_RX_N") (class "Default")
      (node (ref "IC601") (pin "84") (pinfunction "USB3DN_TXDM5_84") (pintype "passive"))
    )
    (net (code "108") (name "/USBMHG_RX_P") (class "Default")
      (node (ref "IC601") (pin "83") (pinfunction "USB3DN_TXDP5_83") (pintype "passive"))
    )
    (net (code "109") (name "/USBMHG_TX_N") (class "Default")
      (node (ref "C644") (pin "2") (pinfunction "2_2") (pintype "passive"))
    )
    (net (code "110") (name "/USBMHG_TX_P") (class "Default")
      (node (ref "C643") (pin "2") (pinfunction "2_2") (pintype "passive"))
    )
    (net (code "111") (name "/USBMHG_XTX_N") (class "Default")
      (node (ref "C644") (pin "1") (pinfunction "1_1") (pintype "passive"))
      (node (ref "IC601") (pin "87") (pinfunction "USB3DN_RXDM5_87") (pintype "passive"))
    )
    (net (code "112") (name "/USBMHG_XTX_P") (class "Default")
      (node (ref "C643") (pin "1") (pinfunction "1_1") (pintype "passive"))
      (node (ref "IC601") (pin "86") (pinfunction "USB3DN_RXDP5_86") (pintype "passive"))
    )
    (net (code "115") (name "/VBUS_DET_G1") (class "Default")
      (node (ref "IC601") (pin "2") (pinfunction "PF30/VBUS_MON_UP_2") (pintype "passive"))
      (node (ref "R615") (pin "1") (pinfunction "1_1") (pintype "passive"))
      (node (ref "R616") (pin "2") (pinfunction "2_2") (pintype "passive"))
    )
    (net (code "116") (name "/XTI_G1") (class "Default")
      (node (ref "C639") (pin "2") (pinfunction "2_2") (pintype "passive"))
      (node (ref "IC601") (pin "98") (pinfunction "XTALI/CLK_IN_98") (pintype "passive"))
      (node (ref "X601") (pin "1") (pinfunction "1_1") (pintype "passive"))
    )
    (net (code "117") (name "/XTO_G1") (class "Default")
      (node (ref "C640") (pin "1") (pinfunction "1_1") (pintype "passive"))
      (node (ref "IC601") (pin "97") (pinfunction "XTALO_97") (pintype "passive"))
      (node (ref "X601") (pin "3") (pinfunction "3_3") (pintype "passive"))
    )
    (net (code "125") (name "GND") (class "Default")
      (node (ref "C601") (pin "2") (pinfunction "2_2") (pintype "passive"))
      (node (ref "C602") (pin "2") (pinfunction "2_2") (pintype "passive"))
      (node (ref "C603") (pin "2") (pinfunction "2_2") (pintype "passive"))
      (node (ref "C604") (pin "2") (pinfunction "2_2") (pintype "passive"))
      (node (ref "C605") (pin "2") (pinfunction "2_2") (pintype "passive"))
      (node (ref "C606") (pin "2") (pinfunction "2_2") (pintype "passive"))
      (node (ref "C607") (pin "2") (pinfunction "2_2") (pintype "passive"))
      (node (ref "C608") (pin "2") (pinfunction "2_2") (pintype "passive"))
      (node (ref "C609") (pin "2") (pinfunction "2_2") (pintype "passive"))
      (node (ref "C610") (pin "2") (pinfunction "2_2") (pintype "passive"))
      (node (ref "C611") (pin "2") (pinfunction "2_2") (pintype "passive"))
      (node (ref "C612") (pin "2") (pinfunction "2_2") (pintype "passive"))
      (node (ref "C613") (pin "2") (pinfunction "2_2") (pintype "passive"))
      (node (ref "C614") (pin "2") (pinfunction "2_2") (pintype "passive"))
      (node (ref "C615") (pin "2") (pinfunction "2_2") (pintype "passive"))
      (node (ref "C616") (pin "2") (pinfunction "2_2") (pintype "passive"))
      (node (ref "C617") (pin "2") (pinfunction "2_2") (pintype "passive"))
      (node (ref "C618") (pin "2") (pinfunction "2_2") (pintype "passive"))
      (node (ref "C619") (pin "2") (pinfunction "2_2") (pintype "passive"))
      (node (ref "C620") (pin "2") (pinfunction "2_2") (pintype "passive"))
      (node (ref "C621") (pin "2") (pinfunction "2_2") (pintype "passive"))
      (node (ref "C622") (pin "2") (pinfunction "2_2") (pintype "passive"))
      (node (ref "C623") (pin "2") (pinfunction "2_2") (pintype "passive"))
      (node (ref "C624") (pin "2") (pinfunction "2_2") (pintype "passive"))
      (node (ref "C625") (pin "2") (pinfunction "2_2") (pintype "passive"))
      (node (ref "C626") (pin "2") (pinfunction "2_2") (pintype "passive"))
      (node (ref "C627") (pin "2") (pinfunction "2_2") (pintype "passive"))
      (node (ref "C628") (pin "2") (pinfunction "2_2") (pintype "passive"))
      (node (ref "C629") (pin "2") (pinfunction "2_2") (pintype "passive"))
      (node (ref "C630") (pin "2") (pinfunction "2_2") (pintype "passive"))
      (node (ref "C631") (pin "2") (pinfunction "2_2") (pintype "passive"))
      (node (ref "C632") (pin "2") (pinfunction "2_2") (pintype "passive"))
      (node (ref "C633") (pin "2") (pinfunction "2_2") (pintype "passive"))
      (node (ref "C634") (pin "2") (pinfunction "2_2") (pintype "passive"))
      (node (ref "C635") (pin "2") (pinfunction "2_2") (pintype "passive"))
      (node (ref "C636") (pin "2") (pinfunction "2_2") (pintype "passive"))
      (node (ref "C637") (pin "2") (pinfunction "2_2") (pintype "passive"))
      (node (ref "C638") (pin "2") (pinfunction "2_2") (pintype "passive"))
      (node (ref "C639") (pin "1") (pinfunction "1_1") (pintype "passive"))
      (node (ref "C640") (pin "2") (pinfunction "2_2") (pintype "passive"))
      (node (ref "IC601") (pin "101") (pinfunction "GND_101") (pintype "passive"))
      (node (ref "IC601") (pin "24") (pinfunction "TESTEN_24") (pintype "passive"))
      (node (ref "IC602") (pin "4") (pinfunction "GND_4") (pintype "passive"))
      (node (ref "IC603") (pin "3") (pinfunction "GND_3") (pintype "passive"))
      (node (ref "R602") (pin "2") (pinfunction "2_2") (pintype "passive"))
      (node (ref "R603") (pin "1") (pinfunction "1_1") (pintype "passive"))
      (node (ref "R604") (pin "1") (pinfunction "1_1") (pintype "passive"))
      (node (ref "R611") (pin "1") (pinfunction "1_1") (pintype "passive"))
      (node (ref "R612") (pin "1") (pinfunction "1_1") (pintype "passive"))
      (node (ref "R613") (pin "1") (pinfunction "1_1") (pintype "passive"))
      (node (ref "R614") (pin "1") (pinfunction "1_1") (pintype "passive"))
      (node (ref "R616") (pin "1") (pinfunction "1_1") (pintype "passive"))
      (node (ref "R617") (pin "1") (pinfunction "1_1") (pintype "passive"))
      (node (ref "R618") (pin "1") (pinfunction "1_1") (pintype "passive"))
      (node (ref "R619") (pin "1") (pinfunction "1_1") (pintype "passive"))
      (node (ref "R620") (pin "1") (pinfunction "1_1") (pintype "passive"))
      (node (ref "R621") (pin "1") (pinfunction "1_1") (pintype "passive"))
      (node (ref "R622") (pin "1") (pinfunction "1_1") (pintype "passive"))
      (node (ref "R623") (pin "1") (pinfunction "1_1") (pintype "passive"))
      (node (ref "R624") (pin "1") (pinfunction "1_1") (pintype "passive"))
      (node (ref "R625") (pin "1") (pinfunction "1_1") (pintype "passive"))
      (node (ref "R626") (pin "1") (pinfunction "1_1") (pintype "passive"))
      (node (ref "R627") (pin "1") (pinfunction "1_1") (pintype "passive"))
      (node (ref "X601") (pin "2") (pinfunction "2_2") (pintype "passive"))
      (node (ref "X601") (pin "4") (pinfunction "4_4") (pintype "passive"))
    )
    (net (code "126") (name "Net-(IC601-RBIAS)") (class "Default")
      (node (ref "IC601") (pin "100") (pinfunction "RBIAS_100") (pintype "passive"))
      (node (ref "R611") (pin "2") (pinfunction "2_2") (pintype "passive"))
    )
    (net (code "127") (name "Net-(IC601-RESET_N)") (class "Default")
      (node (ref "IC601") (pin "1") (pinfunction "RESET_N_1") (pintype "passive"))
      (node (ref "R609") (pin "2") (pinfunction "2_2") (pintype "passive"))
      (node (ref "R614") (pin "2") (pinfunction "2_2") (pintype "passive"))
    )
    (net (code "128") (name "Net-(IC601-TEST1)") (class "Default")
      (node (ref "IC601") (pin "63") (pinfunction "TEST1_63") (pintype "passive"))
      (node (ref "R605") (pin "2") (pinfunction "2_2") (pintype "passive"))
    )
    (net (code "129") (name "Net-(IC601-TEST2)") (class "Default")
      (node (ref "IC601") (pin "64") (pinfunction "TEST2_64") (pintype "passive"))
      (node (ref "R606") (pin "2") (pinfunction "2_2") (pintype "passive"))
    )
    (net (code "130") (name "Net-(IC601-TEST3)") (class "Default")
      (node (ref "IC601") (pin "65") (pinfunction "TEST3_65") (pintype "passive"))
      (node (ref "R607") (pin "2") (pinfunction "2_2") (pintype "passive"))
    )
    (net (code "131") (name "Net-(IC603-A)") (class "Default")
      (node (ref "IC603") (pin "2") (pinfunction "A_2") (pintype "passive"))
      (node (ref "R608") (pin "1") (pinfunction "1_1") (pintype "passive"))
      (node (ref "R613") (pin "2") (pinfunction "2_2") (pintype "passive"))
    )
    (net (code "132") (name "Net-(IC603-B)") (class "Default")
      (node (ref "IC603") (pin "1") (pinfunction "B_1") (pintype "passive"))
      (node (ref "R610") (pin "1") (pinfunction "1_1") (pintype "passive"))
      (node (ref "R612") (pin "2") (pinfunction "2_2") (pintype "passive"))
    )
    (net (code "133") (name "Net-(IC603-Y)") (class "Default")
      (node (ref "IC603") (pin "4") (pinfunction "Y_4") (pintype "passive"))
      (node (ref "R609") (pin "1") (pinfunction "1_1") (pintype "passive"))
    )
    (net (code "134") (name "Net-(R608-Pad2)") (class "Default")
      (node (ref "R608") (pin "2") (pinfunction "2_2") (pintype "passive"))
      (node (ref "SW601") (pin "3") (pinfunction "3_3") (pintype "passive"))
      (node (ref "SW601") (pin "4") (pinfunction "4_4") (pintype "passive"))
    )
    (net (code "135") (name "unconnected-(IC601-ATEST-Pad96)") (class "Default")
      (node (ref "IC601") (pin "96") (pinfunction "ATEST_96") (pintype "passive+no_connect"))
    )
    (net (code "136") (name "unconnected-(IC601-NC-Pad4)") (class "Default")
      (node (ref "IC601") (pin "4") (pinfunction "NC_4") (pintype "passive"))
    )
    (net (code "137") (name "unconnected-(IC601-NC-Pad12)") (class "Default")
      (node (ref "IC601") (pin "12") (pinfunction "NC_12") (pintype "passive"))
    )
    (net (code "138") (name "unconnected-(IC601-NC-Pad13)") (class "Default")
      (node (ref "IC601") (pin "13") (pinfunction "NC_13") (pintype "passive"))
    )
    (net (code "139") (name "unconnected-(IC601-NC-Pad80)") (class "Default")
      (node (ref "IC601") (pin "80") (pinfunction "NC_80") (pintype "passive"))
    )
    (net (code "140") (name "unconnected-(IC601-PF8-Pad49)") (class "Default")
      (node (ref "IC601") (pin "49") (pinfunction "PF8_49") (pintype "passive+no_connect"))
    )
    (net (code "141") (name "unconnected-(IC601-PF9-Pad50)") (class "Default")
      (node (ref "IC601") (pin "50") (pinfunction "PF9_50") (pintype "passive+no_connect"))
    )
    (net (code "142") (name "unconnected-(IC601-PF29-Pad74)") (class "Default")
      (node (ref "IC601") (pin "74") (pinfunction "PF29_74") (pintype "passive"))
    )
    (net (code "143") (name "unconnected-(IC601-USB2DN_DM6{slash}PRT_DIS_M6-Pad41)") (class "Default")
      (node (ref "IC601") (pin "41") (pinfunction "USB2DN_DM6/PRT_DIS_M6_41") (pintype "passive"))
    )
    (net (code "144") (name "unconnected-(IC601-USB2DN_DP6{slash}PRT_DIS_P6-Pad42)") (class "Default")
      (node (ref "IC601") (pin "42") (pinfunction "USB2DN_DP6/PRT_DIS_P6_42") (pintype "passive"))
    )
  )
)
